# PiKVM_USB_Adapter_v1_5.net
KiCad netlist of a schematic drawn in EAGLE
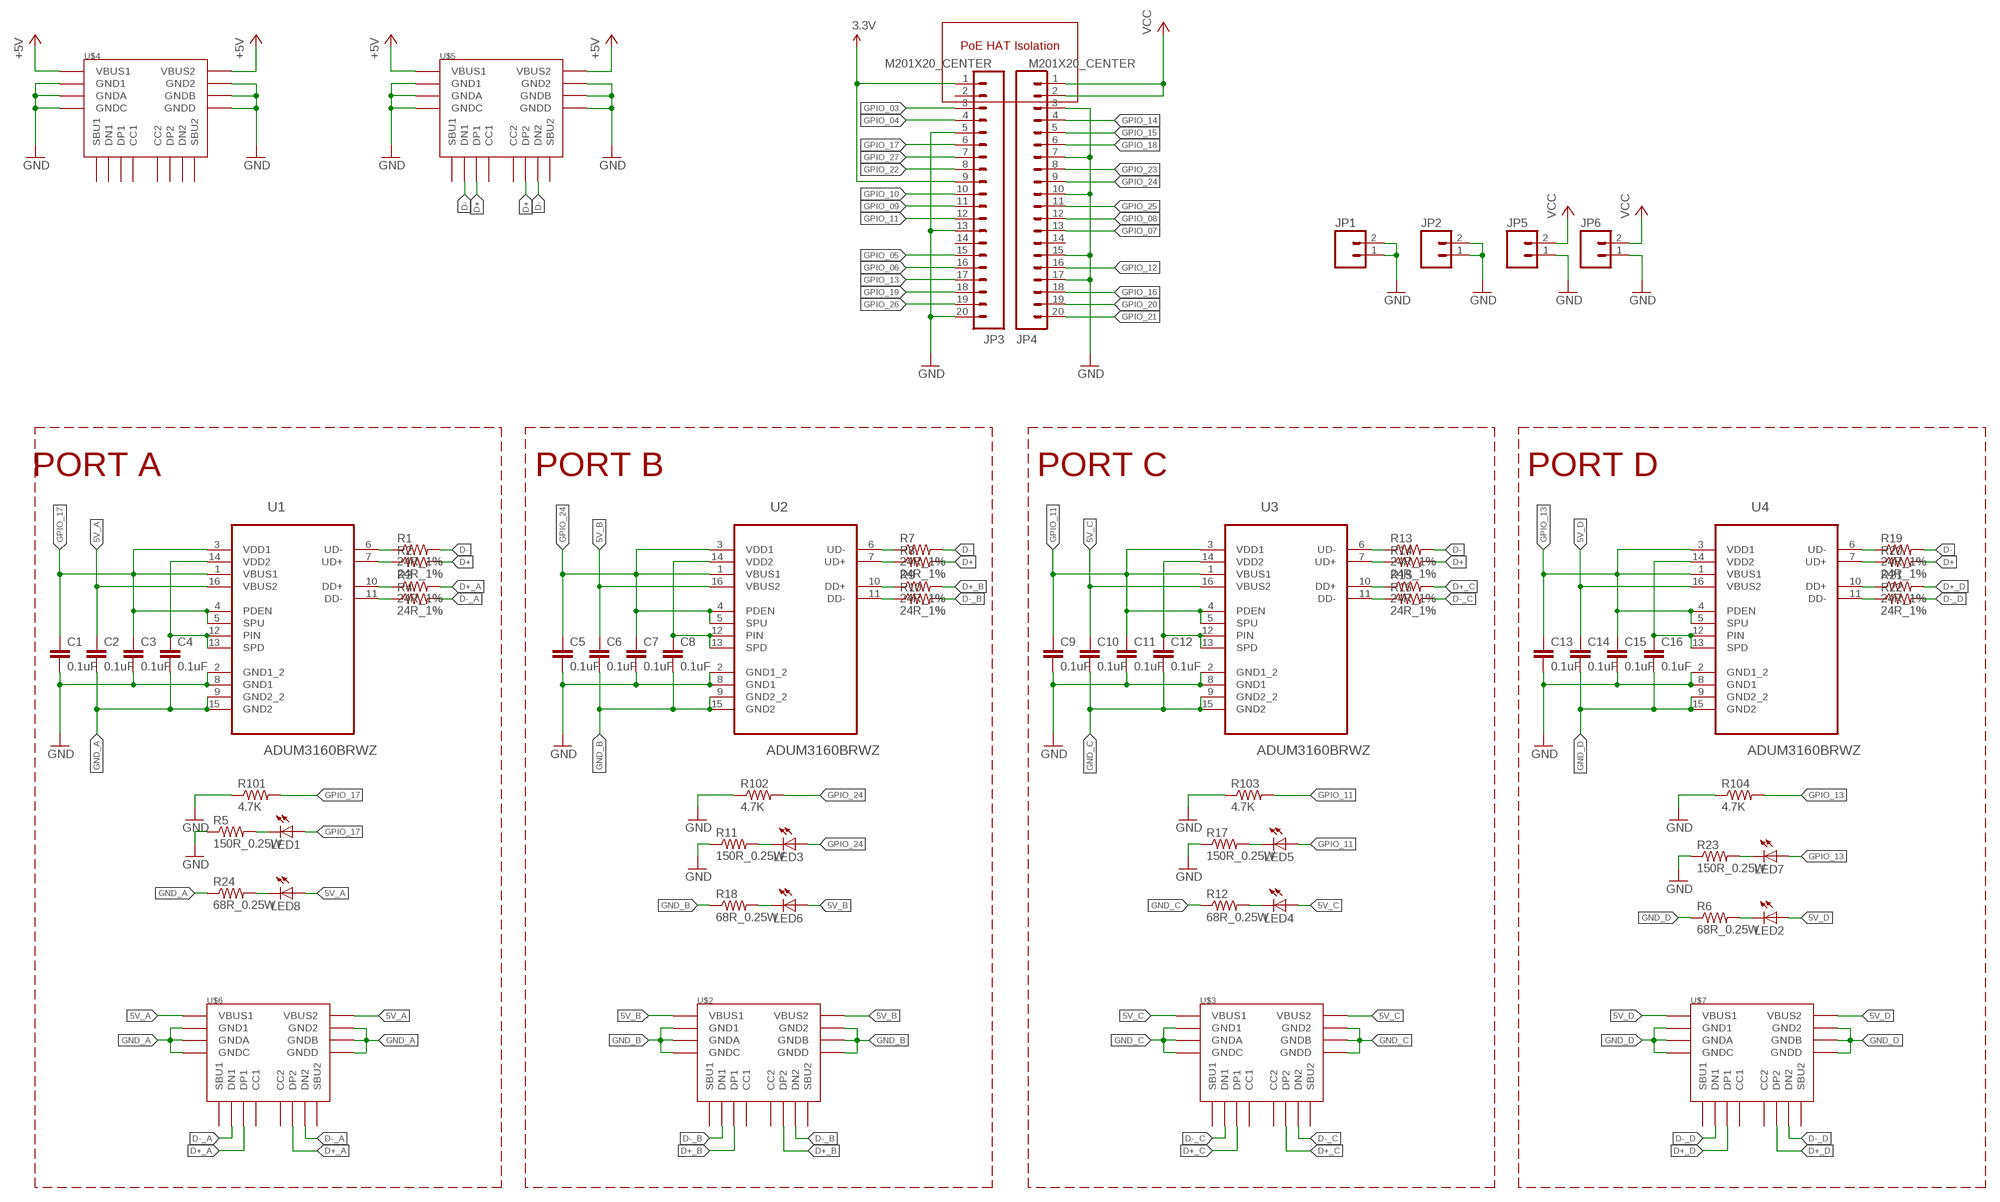
[diagram p0: schematic, sheet 1]

(export (version "E")
  (design (tool "Eeschema 10.0.6"))
  (components
    (comp (ref "C1")
      (value "0.1uF")
      (footprint "eagle-import:0805")
      (libsource (lib "eagle-import") (part "CAP0805"))
    )
    (comp (ref "C2")
      (value "0.1uF")
      (footprint "eagle-import:0805")
      (libsource (lib "eagle-import") (part "CAP0805"))
    )
    (comp (ref "C3")
      (value "0.1uF")
      (footprint "eagle-import:0805")
      (libsource (lib "eagle-import") (part "CAP0805"))
    )
    (comp (ref "C4")
      (value "0.1uF")
      (footprint "eagle-import:0805")
      (libsource (lib "eagle-import") (part "CAP0805"))
    )
    (comp (ref "C5")
      (value "0.1uF")
      (footprint "eagle-import:0805")
      (libsource (lib "eagle-import") (part "CAP0805"))
    )
    (comp (ref "C6")
      (value "0.1uF")
      (footprint "eagle-import:0805")
      (libsource (lib "eagle-import") (part "CAP0805"))
    )
    (comp (ref "C7")
      (value "0.1uF")
      (footprint "eagle-import:0805")
      (libsource (lib "eagle-import") (part "CAP0805"))
    )
    (comp (ref "C8")
      (value "0.1uF")
      (footprint "eagle-import:0805")
      (libsource (lib "eagle-import") (part "CAP0805"))
    )
    (comp (ref "C9")
      (value "0.1uF")
      (footprint "eagle-import:0805")
      (libsource (lib "eagle-import") (part "CAP0805"))
    )
    (comp (ref "C10")
      (value "0.1uF")
      (footprint "eagle-import:0805")
      (libsource (lib "eagle-import") (part "CAP0805"))
    )
    (comp (ref "C11")
      (value "0.1uF")
      (footprint "eagle-import:0805")
      (libsource (lib "eagle-import") (part "CAP0805"))
    )
    (comp (ref "C12")
      (value "0.1uF")
      (footprint "eagle-import:0805")
      (libsource (lib "eagle-import") (part "CAP0805"))
    )
    (comp (ref "C13")
      (value "0.1uF")
      (footprint "eagle-import:0805")
      (libsource (lib "eagle-import") (part "CAP0805"))
    )
    (comp (ref "C14")
      (value "0.1uF")
      (footprint "eagle-import:0805")
      (libsource (lib "eagle-import") (part "CAP0805"))
    )
    (comp (ref "C15")
      (value "0.1uF")
      (footprint "eagle-import:0805")
      (libsource (lib "eagle-import") (part "CAP0805"))
    )
    (comp (ref "C16")
      (value "0.1uF")
      (footprint "eagle-import:0805")
      (libsource (lib "eagle-import") (part "CAP0805"))
    )
    (comp (ref "JP1")
      (value "M02LOCK")
      (footprint "eagle-import:1X02_LOCK")
      (libsource (lib "eagle-import") (part "M02LOCK"))
    )
    (comp (ref "JP2")
      (value "M02LOCK")
      (footprint "eagle-import:1X02_LOCK")
      (libsource (lib "eagle-import") (part "M02LOCK"))
    )
    (comp (ref "JP3")
      (value "M201X20_CENTER")
      (footprint "eagle-import:1X20_CENTER")
      (libsource (lib "eagle-import") (part "M201X20_CENTER"))
    )
    (comp (ref "JP4")
      (value "M201X20_CENTER")
      (footprint "eagle-import:1X20_CENTER")
      (libsource (lib "eagle-import") (part "M201X20_CENTER"))
    )
    (comp (ref "JP5")
      (value "M02LOCK")
      (footprint "eagle-import:1X02_LOCK")
      (libsource (lib "eagle-import") (part "M02LOCK"))
    )
    (comp (ref "JP6")
      (value "M02LOCK")
      (footprint "eagle-import:1X02_LOCK")
      (libsource (lib "eagle-import") (part "M02LOCK"))
    )
    (comp (ref "LED1")
      (value "LED1206")
      (footprint "eagle-import:LED-1206")
      (libsource (lib "eagle-import") (part "LED1206"))
    )
    (comp (ref "LED2")
      (value "LED1206")
      (footprint "eagle-import:LED-1206")
      (libsource (lib "eagle-import") (part "LED1206"))
    )
    (comp (ref "LED3")
      (value "LED1206")
      (footprint "eagle-import:LED-1206")
      (libsource (lib "eagle-import") (part "LED1206"))
    )
    (comp (ref "LED4")
      (value "LED1206")
      (footprint "eagle-import:LED-1206")
      (libsource (lib "eagle-import") (part "LED1206"))
    )
    (comp (ref "LED5")
      (value "LED1206")
      (footprint "eagle-import:LED-1206")
      (libsource (lib "eagle-import") (part "LED1206"))
    )
    (comp (ref "LED6")
      (value "LED1206")
      (footprint "eagle-import:LED-1206")
      (libsource (lib "eagle-import") (part "LED1206"))
    )
    (comp (ref "LED7")
      (value "LED1206")
      (footprint "eagle-import:LED-1206")
      (libsource (lib "eagle-import") (part "LED1206"))
    )
    (comp (ref "LED8")
      (value "LED1206")
      (footprint "eagle-import:LED-1206")
      (libsource (lib "eagle-import") (part "LED1206"))
    )
    (comp (ref "R1")
      (value "24R_1%")
      (footprint "eagle-import:0805")
      (libsource (lib "eagle-import") (part "RESISTOR0805-RES"))
    )
    (comp (ref "R2")
      (value "24R_1%")
      (footprint "eagle-import:0805")
      (libsource (lib "eagle-import") (part "RESISTOR0805-RES"))
    )
    (comp (ref "R3")
      (value "24R_1%")
      (footprint "eagle-import:0805")
      (libsource (lib "eagle-import") (part "RESISTOR0805-RES"))
    )
    (comp (ref "R4")
      (value "24R_1%")
      (footprint "eagle-import:0805")
      (libsource (lib "eagle-import") (part "RESISTOR0805-RES"))
    )
    (comp (ref "R5")
      (value "150R_0.25W")
      (footprint "eagle-import:1206")
      (libsource (lib "eagle-import") (part "RESISTOR1206"))
    )
    (comp (ref "R6")
      (value "68R_0.25W")
      (footprint "eagle-import:1206")
      (libsource (lib "eagle-import") (part "RESISTOR1206"))
    )
    (comp (ref "R7")
      (value "24R_1%")
      (footprint "eagle-import:0805")
      (libsource (lib "eagle-import") (part "RESISTOR0805-RES"))
    )
    (comp (ref "R8")
      (value "24R_1%")
      (footprint "eagle-import:0805")
      (libsource (lib "eagle-import") (part "RESISTOR0805-RES"))
    )
    (comp (ref "R9")
      (value "24R_1%")
      (footprint "eagle-import:0805")
      (libsource (lib "eagle-import") (part "RESISTOR0805-RES"))
    )
    (comp (ref "R10")
      (value "24R_1%")
      (footprint "eagle-import:0805")
      (libsource (lib "eagle-import") (part "RESISTOR0805-RES"))
    )
    (comp (ref "R11")
      (value "150R_0.25W")
      (footprint "eagle-import:1206")
      (libsource (lib "eagle-import") (part "RESISTOR1206"))
    )
    (comp (ref "R12")
      (value "68R_0.25W")
      (footprint "eagle-import:1206")
      (libsource (lib "eagle-import") (part "RESISTOR1206"))
    )
    (comp (ref "R13")
      (value "24R_1%")
      (footprint "eagle-import:0805")
      (libsource (lib "eagle-import") (part "RESISTOR0805-RES"))
    )
    (comp (ref "R14")
      (value "24R_1%")
      (footprint "eagle-import:0805")
      (libsource (lib "eagle-import") (part "RESISTOR0805-RES"))
    )
    (comp (ref "R15")
      (value "24R_1%")
      (footprint "eagle-import:0805")
      (libsource (lib "eagle-import") (part "RESISTOR0805-RES"))
    )
    (comp (ref "R16")
      (value "24R_1%")
      (footprint "eagle-import:0805")
      (libsource (lib "eagle-import") (part "RESISTOR0805-RES"))
    )
    (comp (ref "R17")
      (value "150R_0.25W")
      (footprint "eagle-import:1206")
      (libsource (lib "eagle-import") (part "RESISTOR1206"))
    )
    (comp (ref "R18")
      (value "68R_0.25W")
      (footprint "eagle-import:1206")
      (libsource (lib "eagle-import") (part "RESISTOR1206"))
    )
    (comp (ref "R19")
      (value "24R_1%")
      (footprint "eagle-import:0805")
      (libsource (lib "eagle-import") (part "RESISTOR0805-RES"))
    )
    (comp (ref "R20")
      (value "24R_1%")
      (footprint "eagle-import:0805")
      (libsource (lib "eagle-import") (part "RESISTOR0805-RES"))
    )
    (comp (ref "R21")
      (value "24R_1%")
      (footprint "eagle-import:0805")
      (libsource (lib "eagle-import") (part "RESISTOR0805-RES"))
    )
    (comp (ref "R22")
      (value "24R_1%")
      (footprint "eagle-import:0805")
      (libsource (lib "eagle-import") (part "RESISTOR0805-RES"))
    )
    (comp (ref "R23")
      (value "150R_0.25W")
      (footprint "eagle-import:1206")
      (libsource (lib "eagle-import") (part "RESISTOR1206"))
    )
    (comp (ref "R24")
      (value "68R_0.25W")
      (footprint "eagle-import:1206")
      (libsource (lib "eagle-import") (part "RESISTOR1206"))
    )
    (comp (ref "R101")
      (value "4.7K")
      (footprint "eagle-import:1206")
      (libsource (lib "eagle-import") (part "RESISTOR1206"))
    )
    (comp (ref "R102")
      (value "4.7K")
      (footprint "eagle-import:1206")
      (libsource (lib "eagle-import") (part "RESISTOR1206"))
    )
    (comp (ref "R103")
      (value "4.7K")
      (footprint "eagle-import:1206")
      (libsource (lib "eagle-import") (part "RESISTOR1206"))
    )
    (comp (ref "R104")
      (value "4.7K")
      (footprint "eagle-import:1206")
      (libsource (lib "eagle-import") (part "RESISTOR1206"))
    )
    (comp (ref "U$2")
      (value "USB4110GFA")
      (footprint "eagle-import:GCT_USB4110GFA")
      (libsource (lib "eagle-import") (part "USB4110GFA"))
    )
    (comp (ref "U$3")
      (value "USB4110GFA")
      (footprint "eagle-import:GCT_USB4110GFA")
      (libsource (lib "eagle-import") (part "USB4110GFA"))
    )
    (comp (ref "U$4")
      (value "USB4110GFA")
      (footprint "eagle-import:GCT_USB4110GFA")
      (libsource (lib "eagle-import") (part "USB4110GFA"))
    )
    (comp (ref "U$5")
      (value "USB4110GFA")
      (footprint "eagle-import:GCT_USB4110GFA")
      (libsource (lib "eagle-import") (part "USB4110GFA"))
    )
    (comp (ref "U$6")
      (value "USB4110GFA")
      (footprint "eagle-import:GCT_USB4110GFA")
      (libsource (lib "eagle-import") (part "USB4110GFA"))
    )
    (comp (ref "U$7")
      (value "USB4110GFA")
      (footprint "eagle-import:GCT_USB4110GFA")
      (libsource (lib "eagle-import") (part "USB4110GFA"))
    )
    (comp (ref "U1")
      (value "ADUM3160BRWZ")
      (footprint "eagle-import:SOIC127P1032X265-16N")
      (libsource (lib "eagle-import") (part "ADUM3160BRWZ"))
    )
    (comp (ref "U2")
      (value "ADUM3160BRWZ")
      (footprint "eagle-import:SOIC127P1032X265-16N")
      (libsource (lib "eagle-import") (part "ADUM3160BRWZ"))
    )
    (comp (ref "U3")
      (value "ADUM3160BRWZ")
      (footprint "eagle-import:SOIC127P1032X265-16N")
      (libsource (lib "eagle-import") (part "ADUM3160BRWZ"))
    )
    (comp (ref "U4")
      (value "ADUM3160BRWZ")
      (footprint "eagle-import:SOIC127P1032X265-16N")
      (libsource (lib "eagle-import") (part "ADUM3160BRWZ"))
    )
  )
  (nets
    (net (code "1") (name "+5V") (class "Default")
      (node (ref "U$4") (pin "A4B9") (pinfunction "VBUS1_A4B9") (pintype "power_in"))
      (node (ref "U$4") (pin "B4A9") (pinfunction "VBUS2_B4A9") (pintype "power_in"))
      (node (ref "U$5") (pin "A4B9") (pinfunction "VBUS1_A4B9") (pintype "power_in"))
      (node (ref "U$5") (pin "B4A9") (pinfunction "VBUS2_B4A9") (pintype "power_in"))
    )
    (net (code "2") (name "3.3V") (class "Default")
      (node (ref "JP3") (pin "1") (pinfunction "1_1") (pintype "passive"))
      (node (ref "JP3") (pin "9") (pinfunction "9_9") (pintype "passive"))
    )
    (net (code "3") (name "5V_A") (class "Default")
      (node (ref "C2") (pin "1") (pinfunction "1_1") (pintype "passive"))
      (node (ref "LED8") (pin "A") (pinfunction "A_A") (pintype "passive"))
      (node (ref "U$6") (pin "A4B9") (pinfunction "VBUS1_A4B9") (pintype "power_in"))
      (node (ref "U$6") (pin "B4A9") (pinfunction "VBUS2_B4A9") (pintype "power_in"))
      (node (ref "U1") (pin "16") (pinfunction "VBUS2_16") (pintype "power_in"))
    )
    (net (code "4") (name "5V_B") (class "Default")
      (node (ref "C6") (pin "1") (pinfunction "1_1") (pintype "passive"))
      (node (ref "LED6") (pin "A") (pinfunction "A_A") (pintype "passive"))
      (node (ref "U$2") (pin "A4B9") (pinfunction "VBUS1_A4B9") (pintype "power_in"))
      (node (ref "U$2") (pin "B4A9") (pinfunction "VBUS2_B4A9") (pintype "power_in"))
      (node (ref "U2") (pin "16") (pinfunction "VBUS2_16") (pintype "power_in"))
    )
    (net (code "5") (name "5V_C") (class "Default")
      (node (ref "C10") (pin "1") (pinfunction "1_1") (pintype "passive"))
      (node (ref "LED4") (pin "A") (pinfunction "A_A") (pintype "passive"))
      (node (ref "U$3") (pin "A4B9") (pinfunction "VBUS1_A4B9") (pintype "power_in"))
      (node (ref "U$3") (pin "B4A9") (pinfunction "VBUS2_B4A9") (pintype "power_in"))
      (node (ref "U3") (pin "16") (pinfunction "VBUS2_16") (pintype "power_in"))
    )
    (net (code "6") (name "5V_D") (class "Default")
      (node (ref "C14") (pin "1") (pinfunction "1_1") (pintype "passive"))
      (node (ref "LED2") (pin "A") (pinfunction "A_A") (pintype "passive"))
      (node (ref "U$7") (pin "A4B9") (pinfunction "VBUS1_A4B9") (pintype "power_in"))
      (node (ref "U$7") (pin "B4A9") (pinfunction "VBUS2_B4A9") (pintype "power_in"))
      (node (ref "U4") (pin "16") (pinfunction "VBUS2_16") (pintype "power_in"))
    )
    (net (code "7") (name "D+") (class "Default")
      (node (ref "R14") (pin "2") (pinfunction "2_2") (pintype "passive"))
      (node (ref "R2") (pin "2") (pinfunction "2_2") (pintype "passive"))
      (node (ref "R20") (pin "2") (pinfunction "2_2") (pintype "passive"))
      (node (ref "R8") (pin "2") (pinfunction "2_2") (pintype "passive"))
      (node (ref "U$5") (pin "A6") (pinfunction "DP1_A6") (pintype "bidirectional"))
      (node (ref "U$5") (pin "B6") (pinfunction "DP2_B6") (pintype "bidirectional"))
    )
    (net (code "8") (name "D+_A") (class "Default")
      (node (ref "R3") (pin "2") (pinfunction "2_2") (pintype "passive"))
      (node (ref "U$6") (pin "A6") (pinfunction "DP1_A6") (pintype "bidirectional"))
      (node (ref "U$6") (pin "B6") (pinfunction "DP2_B6") (pintype "bidirectional"))
    )
    (net (code "9") (name "D+_B") (class "Default")
      (node (ref "R9") (pin "2") (pinfunction "2_2") (pintype "passive"))
      (node (ref "U$2") (pin "A6") (pinfunction "DP1_A6") (pintype "bidirectional"))
      (node (ref "U$2") (pin "B6") (pinfunction "DP2_B6") (pintype "bidirectional"))
    )
    (net (code "10") (name "D+_C") (class "Default")
      (node (ref "R15") (pin "2") (pinfunction "2_2") (pintype "passive"))
      (node (ref "U$3") (pin "A6") (pinfunction "DP1_A6") (pintype "bidirectional"))
      (node (ref "U$3") (pin "B6") (pinfunction "DP2_B6") (pintype "bidirectional"))
    )
    (net (code "11") (name "D+_D") (class "Default")
      (node (ref "R21") (pin "2") (pinfunction "2_2") (pintype "passive"))
      (node (ref "U$7") (pin "A6") (pinfunction "DP1_A6") (pintype "bidirectional"))
      (node (ref "U$7") (pin "B6") (pinfunction "DP2_B6") (pintype "bidirectional"))
    )
    (net (code "12") (name "D-") (class "Default")
      (node (ref "R1") (pin "2") (pinfunction "2_2") (pintype "passive"))
      (node (ref "R13") (pin "2") (pinfunction "2_2") (pintype "passive"))
      (node (ref "R19") (pin "2") (pinfunction "2_2") (pintype "passive"))
      (node (ref "R7") (pin "2") (pinfunction "2_2") (pintype "passive"))
      (node (ref "U$5") (pin "A7") (pinfunction "DN1_A7") (pintype "bidirectional"))
      (node (ref "U$5") (pin "B7") (pinfunction "DN2_B7") (pintype "bidirectional"))
    )
    (net (code "13") (name "D-_A") (class "Default")
      (node (ref "R4") (pin "2") (pinfunction "2_2") (pintype "passive"))
      (node (ref "U$6") (pin "A7") (pinfunction "DN1_A7") (pintype "bidirectional"))
      (node (ref "U$6") (pin "B7") (pinfunction "DN2_B7") (pintype "bidirectional"))
    )
    (net (code "14") (name "D-_B") (class "Default")
      (node (ref "R10") (pin "2") (pinfunction "2_2") (pintype "passive"))
      (node (ref "U$2") (pin "A7") (pinfunction "DN1_A7") (pintype "bidirectional"))
      (node (ref "U$2") (pin "B7") (pinfunction "DN2_B7") (pintype "bidirectional"))
    )
    (net (code "15") (name "D-_C") (class "Default")
      (node (ref "R16") (pin "2") (pinfunction "2_2") (pintype "passive"))
      (node (ref "U$3") (pin "A7") (pinfunction "DN1_A7") (pintype "bidirectional"))
      (node (ref "U$3") (pin "B7") (pinfunction "DN2_B7") (pintype "bidirectional"))
    )
    (net (code "16") (name "D-_D") (class "Default")
      (node (ref "R22") (pin "2") (pinfunction "2_2") (pintype "passive"))
      (node (ref "U$7") (pin "A7") (pinfunction "DN1_A7") (pintype "bidirectional"))
      (node (ref "U$7") (pin "B7") (pinfunction "DN2_B7") (pintype "bidirectional"))
    )
    (net (code "17") (name "GND") (class "Default")
      (node (ref "C1") (pin "2") (pinfunction "2_2") (pintype "passive"))
      (node (ref "C11") (pin "2") (pinfunction "2_2") (pintype "passive"))
      (node (ref "C13") (pin "2") (pinfunction "2_2") (pintype "passive"))
      (node (ref "C15") (pin "2") (pinfunction "2_2") (pintype "passive"))
      (node (ref "C3") (pin "2") (pinfunction "2_2") (pintype "passive"))
      (node (ref "C5") (pin "2") (pinfunction "2_2") (pintype "passive"))
      (node (ref "C7") (pin "2") (pinfunction "2_2") (pintype "passive"))
      (node (ref "C9") (pin "2") (pinfunction "2_2") (pintype "passive"))
      (node (ref "JP1") (pin "1") (pinfunction "1_1") (pintype "passive"))
      (node (ref "JP1") (pin "2") (pinfunction "2_2") (pintype "passive"))
      (node (ref "JP2") (pin "1") (pinfunction "1_1") (pintype "passive"))
      (node (ref "JP2") (pin "2") (pinfunction "2_2") (pintype "passive"))
      (node (ref "JP3") (pin "13") (pinfunction "13_13") (pintype "passive"))
      (node (ref "JP3") (pin "20") (pinfunction "20_20") (pintype "passive"))
      (node (ref "JP3") (pin "5") (pinfunction "5_5") (pintype "passive"))
      (node (ref "JP4") (pin "10") (pinfunction "10_10") (pintype "passive"))
      (node (ref "JP4") (pin "15") (pinfunction "15_15") (pintype "passive"))
      (node (ref "JP4") (pin "17") (pinfunction "17_17") (pintype "passive"))
      (node (ref "JP4") (pin "3") (pinfunction "3_3") (pintype "passive"))
      (node (ref "JP4") (pin "7") (pinfunction "7_7") (pintype "passive"))
      (node (ref "JP5") (pin "1") (pinfunction "1_1") (pintype "passive"))
      (node (ref "JP6") (pin "1") (pinfunction "1_1") (pintype "passive"))
      (node (ref "R101") (pin "1") (pinfunction "1_1") (pintype "passive"))
      (node (ref "R102") (pin "1") (pinfunction "1_1") (pintype "passive"))
      (node (ref "R103") (pin "1") (pinfunction "1_1") (pintype "passive"))
      (node (ref "R104") (pin "1") (pinfunction "1_1") (pintype "passive"))
      (node (ref "R11") (pin "1") (pinfunction "1_1") (pintype "passive"))
      (node (ref "R17") (pin "1") (pinfunction "1_1") (pintype "passive"))
      (node (ref "R23") (pin "1") (pinfunction "1_1") (pintype "passive"))
      (node (ref "R5") (pin "1") (pinfunction "1_1") (pintype "passive"))
      (node (ref "U$4") (pin "A1B12") (pinfunction "GND1_A1B12") (pintype "power_in"))
      (node (ref "U$4") (pin "B1A12") (pinfunction "GND2_B1A12") (pintype "power_in"))
      (node (ref "U$4") (pin "GND1") (pinfunction "GNDA_GND1") (pintype "power_in"))
      (node (ref "U$4") (pin "GND2") (pinfunction "GNDB_GND2") (pintype "power_in"))
      (node (ref "U$4") (pin "GND3") (pinfunction "GNDC_GND3") (pintype "power_in"))
      (node (ref "U$4") (pin "GND4") (pinfunction "GNDD_GND4") (pintype "power_in"))
      (node (ref "U$5") (pin "A1B12") (pinfunction "GND1_A1B12") (pintype "power_in"))
      (node (ref "U$5") (pin "B1A12") (pinfunction "GND2_B1A12") (pintype "power_in"))
      (node (ref "U$5") (pin "GND1") (pinfunction "GNDA_GND1") (pintype "power_in"))
      (node (ref "U$5") (pin "GND2") (pinfunction "GNDB_GND2") (pintype "power_in"))
      (node (ref "U$5") (pin "GND3") (pinfunction "GNDC_GND3") (pintype "power_in"))
      (node (ref "U$5") (pin "GND4") (pinfunction "GNDD_GND4") (pintype "power_in"))
      (node (ref "U1") (pin "2") (pinfunction "GND1_2_2") (pintype "passive"))
      (node (ref "U1") (pin "8") (pinfunction "GND1_8") (pintype "passive"))
      (node (ref "U2") (pin "2") (pinfunction "GND1_2_2") (pintype "passive"))
      (node (ref "U2") (pin "8") (pinfunction "GND1_8") (pintype "passive"))
      (node (ref "U3") (pin "2") (pinfunction "GND1_2_2") (pintype "passive"))
      (node (ref "U3") (pin "8") (pinfunction "GND1_8") (pintype "passive"))
      (node (ref "U4") (pin "2") (pinfunction "GND1_2_2") (pintype "passive"))
      (node (ref "U4") (pin "8") (pinfunction "GND1_8") (pintype "passive"))
    )
    (net (code "18") (name "GND_A") (class "Default")
      (node (ref "C2") (pin "2") (pinfunction "2_2") (pintype "passive"))
      (node (ref "C4") (pin "2") (pinfunction "2_2") (pintype "passive"))
      (node (ref "R24") (pin "1") (pinfunction "1_1") (pintype "passive"))
      (node (ref "U$6") (pin "A1B12") (pinfunction "GND1_A1B12") (pintype "power_in"))
      (node (ref "U$6") (pin "B1A12") (pinfunction "GND2_B1A12") (pintype "power_in"))
      (node (ref "U$6") (pin "GND1") (pinfunction "GNDA_GND1") (pintype "power_in"))
      (node (ref "U$6") (pin "GND2") (pinfunction "GNDB_GND2") (pintype "power_in"))
      (node (ref "U$6") (pin "GND3") (pinfunction "GNDC_GND3") (pintype "power_in"))
      (node (ref "U$6") (pin "GND4") (pinfunction "GNDD_GND4") (pintype "power_in"))
      (node (ref "U1") (pin "15") (pinfunction "GND2_15") (pintype "passive"))
      (node (ref "U1") (pin "9") (pinfunction "GND2_2_9") (pintype "passive"))
    )
    (net (code "19") (name "GND_B") (class "Default")
      (node (ref "C6") (pin "2") (pinfunction "2_2") (pintype "passive"))
      (node (ref "C8") (pin "2") (pinfunction "2_2") (pintype "passive"))
      (node (ref "R18") (pin "1") (pinfunction "1_1") (pintype "passive"))
      (node (ref "U$2") (pin "A1B12") (pinfunction "GND1_A1B12") (pintype "power_in"))
      (node (ref "U$2") (pin "B1A12") (pinfunction "GND2_B1A12") (pintype "power_in"))
      (node (ref "U$2") (pin "GND1") (pinfunction "GNDA_GND1") (pintype "power_in"))
      (node (ref "U$2") (pin "GND2") (pinfunction "GNDB_GND2") (pintype "power_in"))
      (node (ref "U$2") (pin "GND3") (pinfunction "GNDC_GND3") (pintype "power_in"))
      (node (ref "U$2") (pin "GND4") (pinfunction "GNDD_GND4") (pintype "power_in"))
      (node (ref "U2") (pin "15") (pinfunction "GND2_15") (pintype "passive"))
      (node (ref "U2") (pin "9") (pinfunction "GND2_2_9") (pintype "passive"))
    )
    (net (code "20") (name "GND_C") (class "Default")
      (node (ref "C10") (pin "2") (pinfunction "2_2") (pintype "passive"))
      (node (ref "C12") (pin "2") (pinfunction "2_2") (pintype "passive"))
      (node (ref "R12") (pin "1") (pinfunction "1_1") (pintype "passive"))
      (node (ref "U$3") (pin "A1B12") (pinfunction "GND1_A1B12") (pintype "power_in"))
      (node (ref "U$3") (pin "B1A12") (pinfunction "GND2_B1A12") (pintype "power_in"))
      (node (ref "U$3") (pin "GND1") (pinfunction "GNDA_GND1") (pintype "power_in"))
      (node (ref "U$3") (pin "GND2") (pinfunction "GNDB_GND2") (pintype "power_in"))
      (node (ref "U$3") (pin "GND3") (pinfunction "GNDC_GND3") (pintype "power_in"))
      (node (ref "U$3") (pin "GND4") (pinfunction "GNDD_GND4") (pintype "power_in"))
      (node (ref "U3") (pin "15") (pinfunction "GND2_15") (pintype "passive"))
      (node (ref "U3") (pin "9") (pinfunction "GND2_2_9") (pintype "passive"))
    )
    (net (code "21") (name "GND_D") (class "Default")
      (node (ref "C14") (pin "2") (pinfunction "2_2") (pintype "passive"))
      (node (ref "C16") (pin "2") (pinfunction "2_2") (pintype "passive"))
      (node (ref "R6") (pin "1") (pinfunction "1_1") (pintype "passive"))
      (node (ref "U$7") (pin "A1B12") (pinfunction "GND1_A1B12") (pintype "power_in"))
      (node (ref "U$7") (pin "B1A12") (pinfunction "GND2_B1A12") (pintype "power_in"))
      (node (ref "U$7") (pin "GND1") (pinfunction "GNDA_GND1") (pintype "power_in"))
      (node (ref "U$7") (pin "GND2") (pinfunction "GNDB_GND2") (pintype "power_in"))
      (node (ref "U$7") (pin "GND3") (pinfunction "GNDC_GND3") (pintype "power_in"))
      (node (ref "U$7") (pin "GND4") (pinfunction "GNDD_GND4") (pintype "power_in"))
      (node (ref "U4") (pin "15") (pinfunction "GND2_15") (pintype "passive"))
      (node (ref "U4") (pin "9") (pinfunction "GND2_2_9") (pintype "passive"))
    )
    (net (code "22") (name "GPIO_03") (class "Default")
      (node (ref "JP3") (pin "3") (pinfunction "3_3") (pintype "passive"))
    )
    (net (code "23") (name "GPIO_04") (class "Default")
      (node (ref "JP3") (pin "4") (pinfunction "4_4") (pintype "passive"))
    )
    (net (code "24") (name "GPIO_05") (class "Default")
      (node (ref "JP3") (pin "15") (pinfunction "15_15") (pintype "passive"))
    )
    (net (code "25") (name "GPIO_06") (class "Default")
      (node (ref "JP3") (pin "16") (pinfunction "16_16") (pintype "passive"))
    )
    (net (code "26") (name "GPIO_07") (class "Default")
      (node (ref "JP4") (pin "13") (pinfunction "13_13") (pintype "passive"))
    )
    (net (code "27") (name "GPIO_08") (class "Default")
      (node (ref "JP4") (pin "12") (pinfunction "12_12") (pintype "passive"))
    )
    (net (code "28") (name "GPIO_09") (class "Default")
      (node (ref "JP3") (pin "11") (pinfunction "11_11") (pintype "passive"))
    )
    (net (code "29") (name "GPIO_10") (class "Default")
      (node (ref "JP3") (pin "10") (pinfunction "10_10") (pintype "passive"))
    )
    (net (code "30") (name "GPIO_11") (class "Default")
      (node (ref "C11") (pin "1") (pinfunction "1_1") (pintype "passive"))
      (node (ref "C9") (pin "1") (pinfunction "1_1") (pintype "passive"))
      (node (ref "JP3") (pin "12") (pinfunction "12_12") (pintype "passive"))
      (node (ref "LED5") (pin "A") (pinfunction "A_A") (pintype "passive"))
      (node (ref "R103") (pin "2") (pinfunction "2_2") (pintype "passive"))
      (node (ref "U3") (pin "1") (pinfunction "VBUS1_1") (pintype "power_in"))
      (node (ref "U3") (pin "3") (pinfunction "VDD1_3") (pintype "power_in"))
      (node (ref "U3") (pin "4") (pinfunction "PDEN_4") (pintype "input"))
      (node (ref "U3") (pin "5") (pinfunction "SPU_5") (pintype "input"))
    )
    (net (code "31") (name "GPIO_12") (class "Default")
      (node (ref "JP4") (pin "16") (pinfunction "16_16") (pintype "passive"))
    )
    (net (code "32") (name "GPIO_13") (class "Default")
      (node (ref "C13") (pin "1") (pinfunction "1_1") (pintype "passive"))
      (node (ref "C15") (pin "1") (pinfunction "1_1") (pintype "passive"))
      (node (ref "JP3") (pin "17") (pinfunction "17_17") (pintype "passive"))
      (node (ref "LED7") (pin "A") (pinfunction "A_A") (pintype "passive"))
      (node (ref "R104") (pin "2") (pinfunction "2_2") (pintype "passive"))
      (node (ref "U4") (pin "1") (pinfunction "VBUS1_1") (pintype "power_in"))
      (node (ref "U4") (pin "3") (pinfunction "VDD1_3") (pintype "power_in"))
      (node (ref "U4") (pin "4") (pinfunction "PDEN_4") (pintype "input"))
      (node (ref "U4") (pin "5") (pinfunction "SPU_5") (pintype "input"))
    )
    (net (code "33") (name "GPIO_14") (class "Default")
      (node (ref "JP4") (pin "4") (pinfunction "4_4") (pintype "passive"))
    )
    (net (code "34") (name "GPIO_15") (class "Default")
      (node (ref "JP4") (pin "5") (pinfunction "5_5") (pintype "passive"))
    )
    (net (code "35") (name "GPIO_16") (class "Default")
      (node (ref "JP4") (pin "18") (pinfunction "18_18") (pintype "passive"))
    )
    (net (code "36") (name "GPIO_17") (class "Default")
      (node (ref "C1") (pin "1") (pinfunction "1_1") (pintype "passive"))
      (node (ref "C3") (pin "1") (pinfunction "1_1") (pintype "passive"))
      (node (ref "JP3") (pin "6") (pinfunction "6_6") (pintype "passive"))
      (node (ref "LED1") (pin "A") (pinfunction "A_A") (pintype "passive"))
      (node (ref "R101") (pin "2") (pinfunction "2_2") (pintype "passive"))
      (node (ref "U1") (pin "1") (pinfunction "VBUS1_1") (pintype "power_in"))
      (node (ref "U1") (pin "3") (pinfunction "VDD1_3") (pintype "power_in"))
      (node (ref "U1") (pin "4") (pinfunction "PDEN_4") (pintype "input"))
      (node (ref "U1") (pin "5") (pinfunction "SPU_5") (pintype "input"))
    )
    (net (code "37") (name "GPIO_18") (class "Default")
      (node (ref "JP4") (pin "6") (pinfunction "6_6") (pintype "passive"))
    )
    (net (code "38") (name "GPIO_19") (class "Default")
      (node (ref "JP3") (pin "18") (pinfunction "18_18") (pintype "passive"))
    )
    (net (code "39") (name "GPIO_20") (class "Default")
      (node (ref "JP4") (pin "19") (pinfunction "19_19") (pintype "passive"))
    )
    (net (code "40") (name "GPIO_21") (class "Default")
      (node (ref "JP4") (pin "20") (pinfunction "20_20") (pintype "passive"))
    )
    (net (code "41") (name "GPIO_22") (class "Default")
      (node (ref "JP3") (pin "8") (pinfunction "8_8") (pintype "passive"))
    )
    (net (code "42") (name "GPIO_23") (class "Default")
      (node (ref "JP4") (pin "8") (pinfunction "8_8") (pintype "passive"))
    )
    (net (code "43") (name "GPIO_24") (class "Default")
      (node (ref "C5") (pin "1") (pinfunction "1_1") (pintype "passive"))
      (node (ref "C7") (pin "1") (pinfunction "1_1") (pintype "passive"))
      (node (ref "JP4") (pin "9") (pinfunction "9_9") (pintype "passive"))
      (node (ref "LED3") (pin "A") (pinfunction "A_A") (pintype "passive"))
      (node (ref "R102") (pin "2") (pinfunction "2_2") (pintype "passive"))
      (node (ref "U2") (pin "1") (pinfunction "VBUS1_1") (pintype "power_in"))
      (node (ref "U2") (pin "3") (pinfunction "VDD1_3") (pintype "power_in"))
      (node (ref "U2") (pin "4") (pinfunction "PDEN_4") (pintype "input"))
      (node (ref "U2") (pin "5") (pinfunction "SPU_5") (pintype "input"))
    )
    (net (code "44") (name "GPIO_25") (class "Default")
      (node (ref "JP4") (pin "11") (pinfunction "11_11") (pintype "passive"))
    )
    (net (code "45") (name "GPIO_26") (class "Default")
      (node (ref "JP3") (pin "19") (pinfunction "19_19") (pintype "passive"))
    )
    (net (code "46") (name "GPIO_27") (class "Default")
      (node (ref "JP3") (pin "7") (pinfunction "7_7") (pintype "passive"))
    )
    (net (code "47") (name "Net-(LED1-PadC)") (class "Default")
      (node (ref "LED1") (pin "C") (pinfunction "C_C") (pintype "passive"))
      (node (ref "R5") (pin "2") (pinfunction "2_2") (pintype "passive"))
    )
    (net (code "48") (name "Net-(LED2-PadC)") (class "Default")
      (node (ref "LED2") (pin "C") (pinfunction "C_C") (pintype "passive"))
      (node (ref "R6") (pin "2") (pinfunction "2_2") (pintype "passive"))
    )
    (net (code "49") (name "Net-(LED3-PadC)") (class "Default")
      (node (ref "LED3") (pin "C") (pinfunction "C_C") (pintype "passive"))
      (node (ref "R11") (pin "2") (pinfunction "2_2") (pintype "passive"))
    )
    (net (code "50") (name "Net-(LED4-PadC)") (class "Default")
      (node (ref "LED4") (pin "C") (pinfunction "C_C") (pintype "passive"))
      (node (ref "R12") (pin "2") (pinfunction "2_2") (pintype "passive"))
    )
    (net (code "51") (name "Net-(LED5-PadC)") (class "Default")
      (node (ref "LED5") (pin "C") (pinfunction "C_C") (pintype "passive"))
      (node (ref "R17") (pin "2") (pinfunction "2_2") (pintype "passive"))
    )
    (net (code "52") (name "Net-(LED6-PadC)") (class "Default")
      (node (ref "LED6") (pin "C") (pinfunction "C_C") (pintype "passive"))
      (node (ref "R18") (pin "2") (pinfunction "2_2") (pintype "passive"))
    )
    (net (code "53") (name "Net-(LED7-PadC)") (class "Default")
      (node (ref "LED7") (pin "C") (pinfunction "C_C") (pintype "passive"))
      (node (ref "R23") (pin "2") (pinfunction "2_2") (pintype "passive"))
    )
    (net (code "54") (name "Net-(LED8-PadC)") (class "Default")
      (node (ref "LED8") (pin "C") (pinfunction "C_C") (pintype "passive"))
      (node (ref "R24") (pin "2") (pinfunction "2_2") (pintype "passive"))
    )
    (net (code "55") (name "Net-(U1-DD+)") (class "Default")
      (node (ref "R3") (pin "1") (pinfunction "1_1") (pintype "passive"))
      (node (ref "U1") (pin "10") (pinfunction "DD+_10") (pintype "bidirectional"))
    )
    (net (code "56") (name "Net-(U1-DD-)") (class "Default")
      (node (ref "R4") (pin "1") (pinfunction "1_1") (pintype "passive"))
      (node (ref "U1") (pin "11") (pinfunction "DD-_11") (pintype "bidirectional"))
    )
    (net (code "57") (name "Net-(U1-PIN)") (class "Default")
      (node (ref "C4") (pin "1") (pinfunction "1_1") (pintype "passive"))
      (node (ref "U1") (pin "12") (pinfunction "PIN_12") (pintype "input"))
      (node (ref "U1") (pin "13") (pinfunction "SPD_13") (pintype "input"))
      (node (ref "U1") (pin "14") (pinfunction "VDD2_14") (pintype "power_in"))
    )
    (net (code "58") (name "Net-(U1-UD+)") (class "Default")
      (node (ref "R2") (pin "1") (pinfunction "1_1") (pintype "passive"))
      (node (ref "U1") (pin "7") (pinfunction "UD+_7") (pintype "bidirectional"))
    )
    (net (code "59") (name "Net-(U1-UD-)") (class "Default")
      (node (ref "R1") (pin "1") (pinfunction "1_1") (pintype "passive"))
      (node (ref "U1") (pin "6") (pinfunction "UD-_6") (pintype "bidirectional"))
    )
    (net (code "60") (name "Net-(U2-DD+)") (class "Default")
      (node (ref "R9") (pin "1") (pinfunction "1_1") (pintype "passive"))
      (node (ref "U2") (pin "10") (pinfunction "DD+_10") (pintype "bidirectional"))
    )
    (net (code "61") (name "Net-(U2-DD-)") (class "Default")
      (node (ref "R10") (pin "1") (pinfunction "1_1") (pintype "passive"))
      (node (ref "U2") (pin "11") (pinfunction "DD-_11") (pintype "bidirectional"))
    )
    (net (code "62") (name "Net-(U2-PIN)") (class "Default")
      (node (ref "C8") (pin "1") (pinfunction "1_1") (pintype "passive"))
      (node (ref "U2") (pin "12") (pinfunction "PIN_12") (pintype "input"))
      (node (ref "U2") (pin "13") (pinfunction "SPD_13") (pintype "input"))
      (node (ref "U2") (pin "14") (pinfunction "VDD2_14") (pintype "power_in"))
    )
    (net (code "63") (name "Net-(U2-UD+)") (class "Default")
      (node (ref "R8") (pin "1") (pinfunction "1_1") (pintype "passive"))
      (node (ref "U2") (pin "7") (pinfunction "UD+_7") (pintype "bidirectional"))
    )
    (net (code "64") (name "Net-(U2-UD-)") (class "Default")
      (node (ref "R7") (pin "1") (pinfunction "1_1") (pintype "passive"))
      (node (ref "U2") (pin "6") (pinfunction "UD-_6") (pintype "bidirectional"))
    )
    (net (code "65") (name "Net-(U3-DD+)") (class "Default")
      (node (ref "R15") (pin "1") (pinfunction "1_1") (pintype "passive"))
      (node (ref "U3") (pin "10") (pinfunction "DD+_10") (pintype "bidirectional"))
    )
    (net (code "66") (name "Net-(U3-DD-)") (class "Default")
      (node (ref "R16") (pin "1") (pinfunction "1_1") (pintype "passive"))
      (node (ref "U3") (pin "11") (pinfunction "DD-_11") (pintype "bidirectional"))
    )
    (net (code "67") (name "Net-(U3-PIN)") (class "Default")
      (node (ref "C12") (pin "1") (pinfunction "1_1") (pintype "passive"))
      (node (ref "U3") (pin "12") (pinfunction "PIN_12") (pintype "input"))
      (node (ref "U3") (pin "13") (pinfunction "SPD_13") (pintype "input"))
      (node (ref "U3") (pin "14") (pinfunction "VDD2_14") (pintype "power_in"))
    )
    (net (code "68") (name "Net-(U3-UD+)") (class "Default")
      (node (ref "R14") (pin "1") (pinfunction "1_1") (pintype "passive"))
      (node (ref "U3") (pin "7") (pinfunction "UD+_7") (pintype "bidirectional"))
    )
    (net (code "69") (name "Net-(U3-UD-)") (class "Default")
      (node (ref "R13") (pin "1") (pinfunction "1_1") (pintype "passive"))
      (node (ref "U3") (pin "6") (pinfunction "UD-_6") (pintype "bidirectional"))
    )
    (net (code "70") (name "Net-(U4-DD+)") (class "Default")
      (node (ref "R21") (pin "1") (pinfunction "1_1") (pintype "passive"))
      (node (ref "U4") (pin "10") (pinfunction "DD+_10") (pintype "bidirectional"))
    )
    (net (code "71") (name "Net-(U4-DD-)") (class "Default")
      (node (ref "R22") (pin "1") (pinfunction "1_1") (pintype "passive"))
      (node (ref "U4") (pin "11") (pinfunction "DD-_11") (pintype "bidirectional"))
    )
    (net (code "72") (name "Net-(U4-PIN)") (class "Default")
      (node (ref "C16") (pin "1") (pinfunction "1_1") (pintype "passive"))
      (node (ref "U4") (pin "12") (pinfunction "PIN_12") (pintype "input"))
      (node (ref "U4") (pin "13") (pinfunction "SPD_13") (pintype "input"))
      (node (ref "U4") (pin "14") (pinfunction "VDD2_14") (pintype "power_in"))
    )
    (net (code "73") (name "Net-(U4-UD+)") (class "Default")
      (node (ref "R20") (pin "1") (pinfunction "1_1") (pintype "passive"))
      (node (ref "U4") (pin "7") (pinfunction "UD+_7") (pintype "bidirectional"))
    )
    (net (code "74") (name "Net-(U4-UD-)") (class "Default")
      (node (ref "R19") (pin "1") (pinfunction "1_1") (pintype "passive"))
      (node (ref "U4") (pin "6") (pinfunction "UD-_6") (pintype "bidirectional"))
    )
    (net (code "75") (name "VCC") (class "Default")
      (node (ref "JP4") (pin "1") (pinfunction "1_1") (pintype "passive"))
      (node (ref "JP4") (pin "2") (pinfunction "2_2") (pintype "passive"))
      (node (ref "JP5") (pin "2") (pinfunction "2_2") (pintype "passive"))
      (node (ref "JP6") (pin "2") (pinfunction "2_2") (pintype "passive"))
    )
    (net (code "76") (name "unconnected-(JP3-Pad2)") (class "Default")
      (node (ref "JP3") (pin "2") (pinfunction "2_2") (pintype "passive"))
    )
    (net (code "77") (name "unconnected-(JP3-Pad14)") (class "Default")
      (node (ref "JP3") (pin "14") (pinfunction "14_14") (pintype "passive"))
    )
    (net (code "78") (name "unconnected-(JP4-Pad14)") (class "Default")
      (node (ref "JP4") (pin "14") (pinfunction "14_14") (pintype "passive"))
    )
    (net (code "79") (name "unconnected-(U$2-CC1-PadA5)") (class "Default")
      (node (ref "U$2") (pin "A5") (pinfunction "CC1_A5") (pintype "bidirectional"))
    )
    (net (code "80") (name "unconnected-(U$2-CC2-PadB5)") (class "Default")
      (node (ref "U$2") (pin "B5") (pinfunction "CC2_B5") (pintype "bidirectional"))
    )
    (net (code "81") (name "unconnected-(U$2-SBU1-PadA8)") (class "Default")
      (node (ref "U$2") (pin "A8") (pinfunction "SBU1_A8") (pintype "bidirectional"))
    )
    (net (code "82") (name "unconnected-(U$2-SBU2-PadB8)") (class "Default")
      (node (ref "U$2") (pin "B8") (pinfunction "SBU2_B8") (pintype "bidirectional"))
    )
    (net (code "83") (name "unconnected-(U$3-CC1-PadA5)") (class "Default")
      (node (ref "U$3") (pin "A5") (pinfunction "CC1_A5") (pintype "bidirectional"))
    )
    (net (code "84") (name "unconnected-(U$3-CC2-PadB5)") (class "Default")
      (node (ref "U$3") (pin "B5") (pinfunction "CC2_B5") (pintype "bidirectional"))
    )
    (net (code "85") (name "unconnected-(U$3-SBU1-PadA8)") (class "Default")
      (node (ref "U$3") (pin "A8") (pinfunction "SBU1_A8") (pintype "bidirectional"))
    )
    (net (code "86") (name "unconnected-(U$3-SBU2-PadB8)") (class "Default")
      (node (ref "U$3") (pin "B8") (pinfunction "SBU2_B8") (pintype "bidirectional"))
    )
    (net (code "87") (name "unconnected-(U$4-CC1-PadA5)") (class "Default")
      (node (ref "U$4") (pin "A5") (pinfunction "CC1_A5") (pintype "bidirectional"))
    )
    (net (code "88") (name "unconnected-(U$4-CC2-PadB5)") (class "Default")
      (node (ref "U$4") (pin "B5") (pinfunction "CC2_B5") (pintype "bidirectional"))
    )
    (net (code "89") (name "unconnected-(U$4-DN1-PadA7)") (class "Default")
      (node (ref "U$4") (pin "A7") (pinfunction "DN1_A7") (pintype "bidirectional"))
    )
    (net (code "90") (name "unconnected-(U$4-DN2-PadB7)") (class "Default")
      (node (ref "U$4") (pin "B7") (pinfunction "DN2_B7") (pintype "bidirectional"))
    )
    (net (code "91") (name "unconnected-(U$4-DP1-PadA6)") (class "Default")
      (node (ref "U$4") (pin "A6") (pinfunction "DP1_A6") (pintype "bidirectional"))
    )
    (net (code "92") (name "unconnected-(U$4-DP2-PadB6)") (class "Default")
      (node (ref "U$4") (pin "B6") (pinfunction "DP2_B6") (pintype "bidirectional"))
    )
    (net (code "93") (name "unconnected-(U$4-SBU1-PadA8)") (class "Default")
      (node (ref "U$4") (pin "A8") (pinfunction "SBU1_A8") (pintype "bidirectional"))
    )
    (net (code "94") (name "unconnected-(U$4-SBU2-PadB8)") (class "Default")
      (node (ref "U$4") (pin "B8") (pinfunction "SBU2_B8") (pintype "bidirectional"))
    )
    (net (code "95") (name "unconnected-(U$5-CC1-PadA5)") (class "Default")
      (node (ref "U$5") (pin "A5") (pinfunction "CC1_A5") (pintype "bidirectional"))
    )
    (net (code "96") (name "unconnected-(U$5-CC2-PadB5)") (class "Default")
      (node (ref "U$5") (pin "B5") (pinfunction "CC2_B5") (pintype "bidirectional"))
    )
    (net (code "97") (name "unconnected-(U$5-SBU1-PadA8)") (class "Default")
      (node (ref "U$5") (pin "A8") (pinfunction "SBU1_A8") (pintype "bidirectional"))
    )
    (net (code "98") (name "unconnected-(U$5-SBU2-PadB8)") (class "Default")
      (node (ref "U$5") (pin "B8") (pinfunction "SBU2_B8") (pintype "bidirectional"))
    )
    (net (code "99") (name "unconnected-(U$6-CC1-PadA5)") (class "Default")
      (node (ref "U$6") (pin "A5") (pinfunction "CC1_A5") (pintype "bidirectional"))
    )
    (net (code "100") (name "unconnected-(U$6-CC2-PadB5)") (class "Default")
      (node (ref "U$6") (pin "B5") (pinfunction "CC2_B5") (pintype "bidirectional"))
    )
    (net (code "101") (name "unconnected-(U$6-SBU1-PadA8)") (class "Default")
      (node (ref "U$6") (pin "A8") (pinfunction "SBU1_A8") (pintype "bidirectional"))
    )
    (net (code "102") (name "unconnected-(U$6-SBU2-PadB8)") (class "Default")
      (node (ref "U$6") (pin "B8") (pinfunction "SBU2_B8") (pintype "bidirectional"))
    )
    (net (code "103") (name "unconnected-(U$7-CC1-PadA5)") (class "Default")
      (node (ref "U$7") (pin "A5") (pinfunction "CC1_A5") (pintype "bidirectional"))
    )
    (net (code "104") (name "unconnected-(U$7-CC2-PadB5)") (class "Default")
      (node (ref "U$7") (pin "B5") (pinfunction "CC2_B5") (pintype "bidirectional"))
    )
    (net (code "105") (name "unconnected-(U$7-SBU1-PadA8)") (class "Default")
      (node (ref "U$7") (pin "A8") (pinfunction "SBU1_A8") (pintype "bidirectional"))
    )
    (net (code "106") (name "unconnected-(U$7-SBU2-PadB8)") (class "Default")
      (node (ref "U$7") (pin "B8") (pinfunction "SBU2_B8") (pintype "bidirectional"))
    )
  )
)
